# Sheet1.net
KiCad netlist of a schematic drawn in Altium Designer
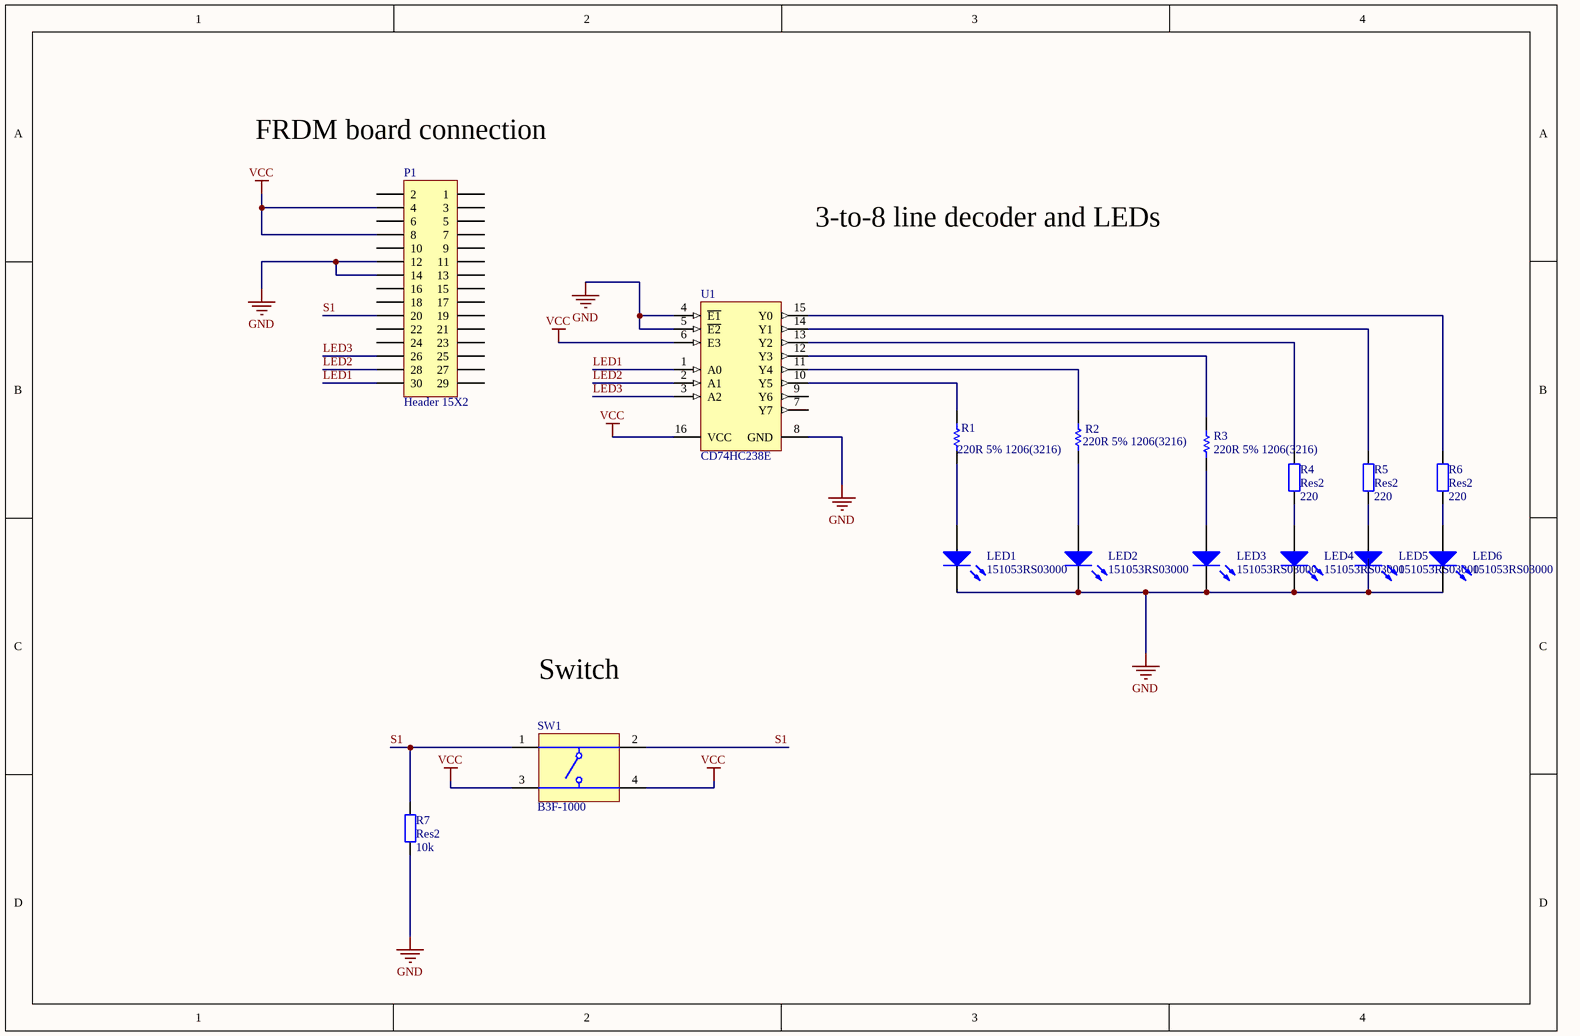
[diagram p0: Sheet1.SchDoc]

(export (version "E")
  (design (tool "Eeschema 10.0.6"))
  (components
    (comp (ref "LED1")
      (value "151053RS03000")
      (footprint "Type 5mm")
      (description "THT LED round mono-color waterclear,  WL-TMRW ,Red")
      (fields (field (name "MANUFACTURER") "Wuerth Elektronik"))
      (libsource (lib "Altium Content Vault") (part "WE-LED_K1A2-2"))
    )
    (comp (ref "LED2")
      (value "151053RS03000")
      (footprint "Type 5mm")
      (description "THT LED round mono-color waterclear,  WL-TMRW ,Red")
      (fields (field (name "MANUFACTURER") "Wuerth Elektronik"))
      (libsource (lib "Altium Content Vault") (part "WE-LED_K1A2-2"))
    )
    (comp (ref "LED3")
      (value "151053RS03000")
      (footprint "Type 5mm")
      (description "THT LED round mono-color waterclear,  WL-TMRW ,Red")
      (fields (field (name "MANUFACTURER") "Wuerth Elektronik"))
      (libsource (lib "Altium Content Vault") (part "WE-LED_K1A2-2"))
    )
    (comp (ref "LED4")
      (value "151053RS03000")
      (footprint "Type 5mm")
      (description "THT LED round mono-color waterclear,  WL-TMRW ,Red")
      (fields (field (name "MANUFACTURER") "Wuerth Elektronik"))
      (libsource (lib "Altium Content Vault") (part "WE-LED_K1A2-2"))
    )
    (comp (ref "LED5")
      (value "151053RS03000")
      (footprint "Type 5mm")
      (description "THT LED round mono-color waterclear,  WL-TMRW ,Red")
      (fields (field (name "MANUFACTURER") "Wuerth Elektronik"))
      (libsource (lib "Altium Content Vault") (part "WE-LED_K1A2-2"))
    )
    (comp (ref "LED6")
      (value "151053RS03000")
      (footprint "Type 5mm")
      (description "THT LED round mono-color waterclear,  WL-TMRW ,Red")
      (fields (field (name "MANUFACTURER") "Wuerth Elektronik"))
      (libsource (lib "Altium Content Vault") (part "WE-LED_K1A2-2"))
    )
    (comp (ref "P1")
      (value "Header 15X2")
      (footprint "HDR2X15")
      (description "Header, 15-Pin, Dual row")
      (fields (field (name "PUBLISHER") "Altium Limited"))
      (libsource (lib "Miscellaneous Connectors") (part "Header 15X2"))
    )
    (comp (ref "R1")
      (value "220R 5% 1206(3216)")
      (footprint "RESC1206(3216)_M")
      (description "220R 0.25W 5% 1206 (3216 Metric)  SMD")
      (fields (field (name "POWER") "0.25 W") (field (name "TOLERANCE") "5 %"))
      (libsource (lib "Altium Content Vault") (part "RES"))
    )
    (comp (ref "R2")
      (value "220R 5% 1206(3216)")
      (footprint "RESC1206(3216)_M")
      (description "220R 0.25W 5% 1206 (3216 Metric)  SMD")
      (fields (field (name "POWER") "0.25 W") (field (name "TOLERANCE") "5 %"))
      (libsource (lib "Altium Content Vault") (part "RES"))
    )
    (comp (ref "R3")
      (value "220R 5% 1206(3216)")
      (footprint "RESC1206(3216)_M")
      (description "220R 0.25W 5% 1206 (3216 Metric)  SMD")
      (fields (field (name "POWER") "0.25 W") (field (name "TOLERANCE") "5 %"))
      (libsource (lib "Altium Content Vault") (part "RES"))
    )
    (comp (ref "R4")
      (value "Res2")
      (footprint "AXIAL-0.4")
      (description "Resistor")
      (fields (field (name "ALTIUM_VALUE") "220") (field (name "PUBLISHER") "Altium Limited"))
      (libsource (lib "Miscellaneous Devices") (part "Res2"))
    )
    (comp (ref "R5")
      (value "Res2")
      (footprint "AXIAL-0.4")
      (description "Resistor")
      (fields (field (name "ALTIUM_VALUE") "220") (field (name "PUBLISHER") "Altium Limited"))
      (libsource (lib "Miscellaneous Devices") (part "Res2"))
    )
    (comp (ref "R6")
      (value "Res2")
      (footprint "AXIAL-0.4")
      (description "Resistor")
      (fields (field (name "ALTIUM_VALUE") "220") (field (name "PUBLISHER") "Altium Limited"))
      (libsource (lib "Miscellaneous Devices") (part "Res2"))
    )
    (comp (ref "R7")
      (value "Res2")
      (footprint "AXIAL-0.4")
      (description "Resistor")
      (fields (field (name "ALTIUM_VALUE") "10k") (field (name "PUBLISHER") "Altium Limited"))
      (libsource (lib "Miscellaneous Devices") (part "Res2"))
    )
    (comp (ref "SW1")
      (value "B3F-1000")
      (footprint "OMRON-B3F-1000-4_V")
      (description "Tactile Switch, SPST-NO, 0.05 A, 5 to 24 V, -25 to 70 degC, 4-Pin THD, RoHS, Bulk")
      (libsource (lib "Altium Content Vault") (part "SW-SPST-4_A"))
    )
    (comp (ref "U1")
      (value "CD74HC238E")
      (footprint "N0016A")
      (description "High Speed CMOS Logic 3-to-8 Line Decoder Demultiplexer Inverting and Non-Inverting, N0016A, TUBE")
      (fields
        (field (name "MANUFACTURER") "Texas Instruments")
        (field (name "GENERIC PART NUMBER") "CD74HC238")
      )
      (libsource (lib "Altium Content Vault") (part "TI-CD54_74HCX238-16"))
    )
  )
  (nets
    (net (code "1") (name "/LED1") (class "Default")
      (node (ref "P1") (pin "30") (pinfunction "30_30") (pintype "passive"))
      (node (ref "U1") (pin "1") (pinfunction "A0_1") (pintype "input"))
    )
    (net (code "2") (name "/LED2") (class "Default")
      (node (ref "P1") (pin "28") (pinfunction "28_28") (pintype "passive"))
      (node (ref "U1") (pin "2") (pinfunction "A1_2") (pintype "input"))
    )
    (net (code "3") (name "/LED3") (class "Default")
      (node (ref "P1") (pin "26") (pinfunction "26_26") (pintype "passive"))
      (node (ref "U1") (pin "3") (pinfunction "A2_3") (pintype "input"))
    )
    (net (code "4") (name "/S1") (class "Default")
      (node (ref "P1") (pin "20") (pinfunction "20_20") (pintype "passive"))
      (node (ref "R7") (pin "2") (pinfunction "2_2") (pintype "passive"))
      (node (ref "SW1") (pin "1") (pinfunction "1_1") (pintype "passive"))
      (node (ref "SW1") (pin "2") (pinfunction "2_2") (pintype "passive"))
    )
    (net (code "5") (name "GND") (class "Default")
      (node (ref "LED1") (pin "1") (pinfunction "K_1") (pintype "passive"))
      (node (ref "LED2") (pin "1") (pinfunction "K_1") (pintype "passive"))
      (node (ref "LED3") (pin "1") (pinfunction "K_1") (pintype "passive"))
      (node (ref "LED4") (pin "1") (pinfunction "K_1") (pintype "passive"))
      (node (ref "LED5") (pin "1") (pinfunction "K_1") (pintype "passive"))
      (node (ref "LED6") (pin "1") (pinfunction "K_1") (pintype "passive"))
      (node (ref "P1") (pin "12") (pinfunction "12_12") (pintype "passive"))
      (node (ref "P1") (pin "14") (pinfunction "14_14") (pintype "passive"))
      (node (ref "R7") (pin "1") (pinfunction "1_1") (pintype "passive"))
      (node (ref "U1") (pin "4") (pinfunction "~{E1}_4") (pintype "input"))
      (node (ref "U1") (pin "5") (pinfunction "~{E2}_5") (pintype "input"))
      (node (ref "U1") (pin "8") (pinfunction "GND_8") (pintype "power_in"))
    )
    (net (code "6") (name "Net-(LED1-A)") (class "Default")
      (node (ref "LED1") (pin "2") (pinfunction "A_2") (pintype "passive"))
      (node (ref "R1") (pin "1") (pinfunction "1_1") (pintype "passive"))
    )
    (net (code "7") (name "Net-(LED2-A)") (class "Default")
      (node (ref "LED2") (pin "2") (pinfunction "A_2") (pintype "passive"))
      (node (ref "R2") (pin "1") (pinfunction "1_1") (pintype "passive"))
    )
    (net (code "8") (name "Net-(LED3-A)") (class "Default")
      (node (ref "LED3") (pin "2") (pinfunction "A_2") (pintype "passive"))
      (node (ref "R3") (pin "1") (pinfunction "1_1") (pintype "passive"))
    )
    (net (code "9") (name "Net-(LED4-A)") (class "Default")
      (node (ref "LED4") (pin "2") (pinfunction "A_2") (pintype "passive"))
      (node (ref "R4") (pin "1") (pinfunction "1_1") (pintype "passive"))
    )
    (net (code "10") (name "Net-(LED5-A)") (class "Default")
      (node (ref "LED5") (pin "2") (pinfunction "A_2") (pintype "passive"))
      (node (ref "R5") (pin "1") (pinfunction "1_1") (pintype "passive"))
    )
    (net (code "11") (name "Net-(LED6-A)") (class "Default")
      (node (ref "LED6") (pin "2") (pinfunction "A_2") (pintype "passive"))
      (node (ref "R6") (pin "1") (pinfunction "1_1") (pintype "passive"))
    )
    (net (code "12") (name "Net-(U1-Y0)") (class "Default")
      (node (ref "R6") (pin "2") (pinfunction "2_2") (pintype "passive"))
      (node (ref "U1") (pin "15") (pinfunction "Y0_15") (pintype "output"))
    )
    (net (code "13") (name "Net-(U1-Y1)") (class "Default")
      (node (ref "R5") (pin "2") (pinfunction "2_2") (pintype "passive"))
      (node (ref "U1") (pin "14") (pinfunction "Y1_14") (pintype "output"))
    )
    (net (code "14") (name "Net-(U1-Y2)") (class "Default")
      (node (ref "R4") (pin "2") (pinfunction "2_2") (pintype "passive"))
      (node (ref "U1") (pin "13") (pinfunction "Y2_13") (pintype "output"))
    )
    (net (code "15") (name "Net-(U1-Y3)") (class "Default")
      (node (ref "R3") (pin "2") (pinfunction "2_2") (pintype "passive"))
      (node (ref "U1") (pin "12") (pinfunction "Y3_12") (pintype "output"))
    )
    (net (code "16") (name "Net-(U1-Y4)") (class "Default")
      (node (ref "R2") (pin "2") (pinfunction "2_2") (pintype "passive"))
      (node (ref "U1") (pin "11") (pinfunction "Y4_11") (pintype "output"))
    )
    (net (code "17") (name "Net-(U1-Y5)") (class "Default")
      (node (ref "R1") (pin "2") (pinfunction "2_2") (pintype "passive"))
      (node (ref "U1") (pin "10") (pinfunction "Y5_10") (pintype "output"))
    )
    (net (code "18") (name "VCC") (class "Default")
      (node (ref "P1") (pin "4") (pinfunction "4_4") (pintype "passive"))
      (node (ref "P1") (pin "8") (pinfunction "8_8") (pintype "passive"))
      (node (ref "SW1") (pin "3") (pinfunction "3_3") (pintype "passive"))
      (node (ref "SW1") (pin "4") (pinfunction "4_4") (pintype "passive"))
      (node (ref "U1") (pin "16") (pinfunction "VCC_16") (pintype "power_in"))
      (node (ref "U1") (pin "6") (pinfunction "E3_6") (pintype "input"))
    )
    (net (code "19") (name "unconnected-(P1-Pad1)") (class "Default")
      (node (ref "P1") (pin "1") (pinfunction "1_1") (pintype "passive"))
    )
    (net (code "20") (name "unconnected-(P1-Pad2)") (class "Default")
      (node (ref "P1") (pin "2") (pinfunction "2_2") (pintype "passive"))
    )
    (net (code "21") (name "unconnected-(P1-Pad3)") (class "Default")
      (node (ref "P1") (pin "3") (pinfunction "3_3") (pintype "passive"))
    )
    (net (code "22") (name "unconnected-(P1-Pad5)") (class "Default")
      (node (ref "P1") (pin "5") (pinfunction "5_5") (pintype "passive"))
    )
    (net (code "23") (name "unconnected-(P1-Pad6)") (class "Default")
      (node (ref "P1") (pin "6") (pinfunction "6_6") (pintype "passive"))
    )
    (net (code "24") (name "unconnected-(P1-Pad7)") (class "Default")
      (node (ref "P1") (pin "7") (pinfunction "7_7") (pintype "passive"))
    )
    (net (code "25") (name "unconnected-(P1-Pad9)") (class "Default")
      (node (ref "P1") (pin "9") (pinfunction "9_9") (pintype "passive"))
    )
    (net (code "26") (name "unconnected-(P1-Pad10)") (class "Default")
      (node (ref "P1") (pin "10") (pinfunction "10_10") (pintype "passive"))
    )
    (net (code "27") (name "unconnected-(P1-Pad11)") (class "Default")
      (node (ref "P1") (pin "11") (pinfunction "11_11") (pintype "passive"))
    )
    (net (code "28") (name "unconnected-(P1-Pad13)") (class "Default")
      (node (ref "P1") (pin "13") (pinfunction "13_13") (pintype "passive"))
    )
    (net (code "29") (name "unconnected-(P1-Pad15)") (class "Default")
      (node (ref "P1") (pin "15") (pinfunction "15_15") (pintype "passive"))
    )
    (net (code "30") (name "unconnected-(P1-Pad16)") (class "Default")
      (node (ref "P1") (pin "16") (pinfunction "16_16") (pintype "passive"))
    )
    (net (code "31") (name "unconnected-(P1-Pad17)") (class "Default")
      (node (ref "P1") (pin "17") (pinfunction "17_17") (pintype "passive"))
    )
    (net (code "32") (name "unconnected-(P1-Pad18)") (class "Default")
      (node (ref "P1") (pin "18") (pinfunction "18_18") (pintype "passive"))
    )
    (net (code "33") (name "unconnected-(P1-Pad19)") (class "Default")
      (node (ref "P1") (pin "19") (pinfunction "19_19") (pintype "passive"))
    )
    (net (code "34") (name "unconnected-(P1-Pad21)") (class "Default")
      (node (ref "P1") (pin "21") (pinfunction "21_21") (pintype "passive"))
    )
    (net (code "35") (name "unconnected-(P1-Pad22)") (class "Default")
      (node (ref "P1") (pin "22") (pinfunction "22_22") (pintype "passive"))
    )
    (net (code "36") (name "unconnected-(P1-Pad23)") (class "Default")
      (node (ref "P1") (pin "23") (pinfunction "23_23") (pintype "passive"))
    )
    (net (code "37") (name "unconnected-(P1-Pad24)") (class "Default")
      (node (ref "P1") (pin "24") (pinfunction "24_24") (pintype "passive"))
    )
    (net (code "38") (name "unconnected-(P1-Pad25)") (class "Default")
      (node (ref "P1") (pin "25") (pinfunction "25_25") (pintype "passive"))
    )
    (net (code "39") (name "unconnected-(P1-Pad27)") (class "Default")
      (node (ref "P1") (pin "27") (pinfunction "27_27") (pintype "passive"))
    )
    (net (code "40") (name "unconnected-(P1-Pad29)") (class "Default")
      (node (ref "P1") (pin "29") (pinfunction "29_29") (pintype "passive"))
    )
    (net (code "41") (name "unconnected-(U1-Y6-Pad9)") (class "Default")
      (node (ref "U1") (pin "9") (pinfunction "Y6_9") (pintype "output"))
    )
    (net (code "42") (name "unconnected-(U1-Y7-Pad7)") (class "Default")
      (node (ref "U1") (pin "7") (pinfunction "Y7_7") (pintype "output"))
    )
  )
)
